# battery5_3.net
KiCad netlist of a schematic drawn in EAGLE
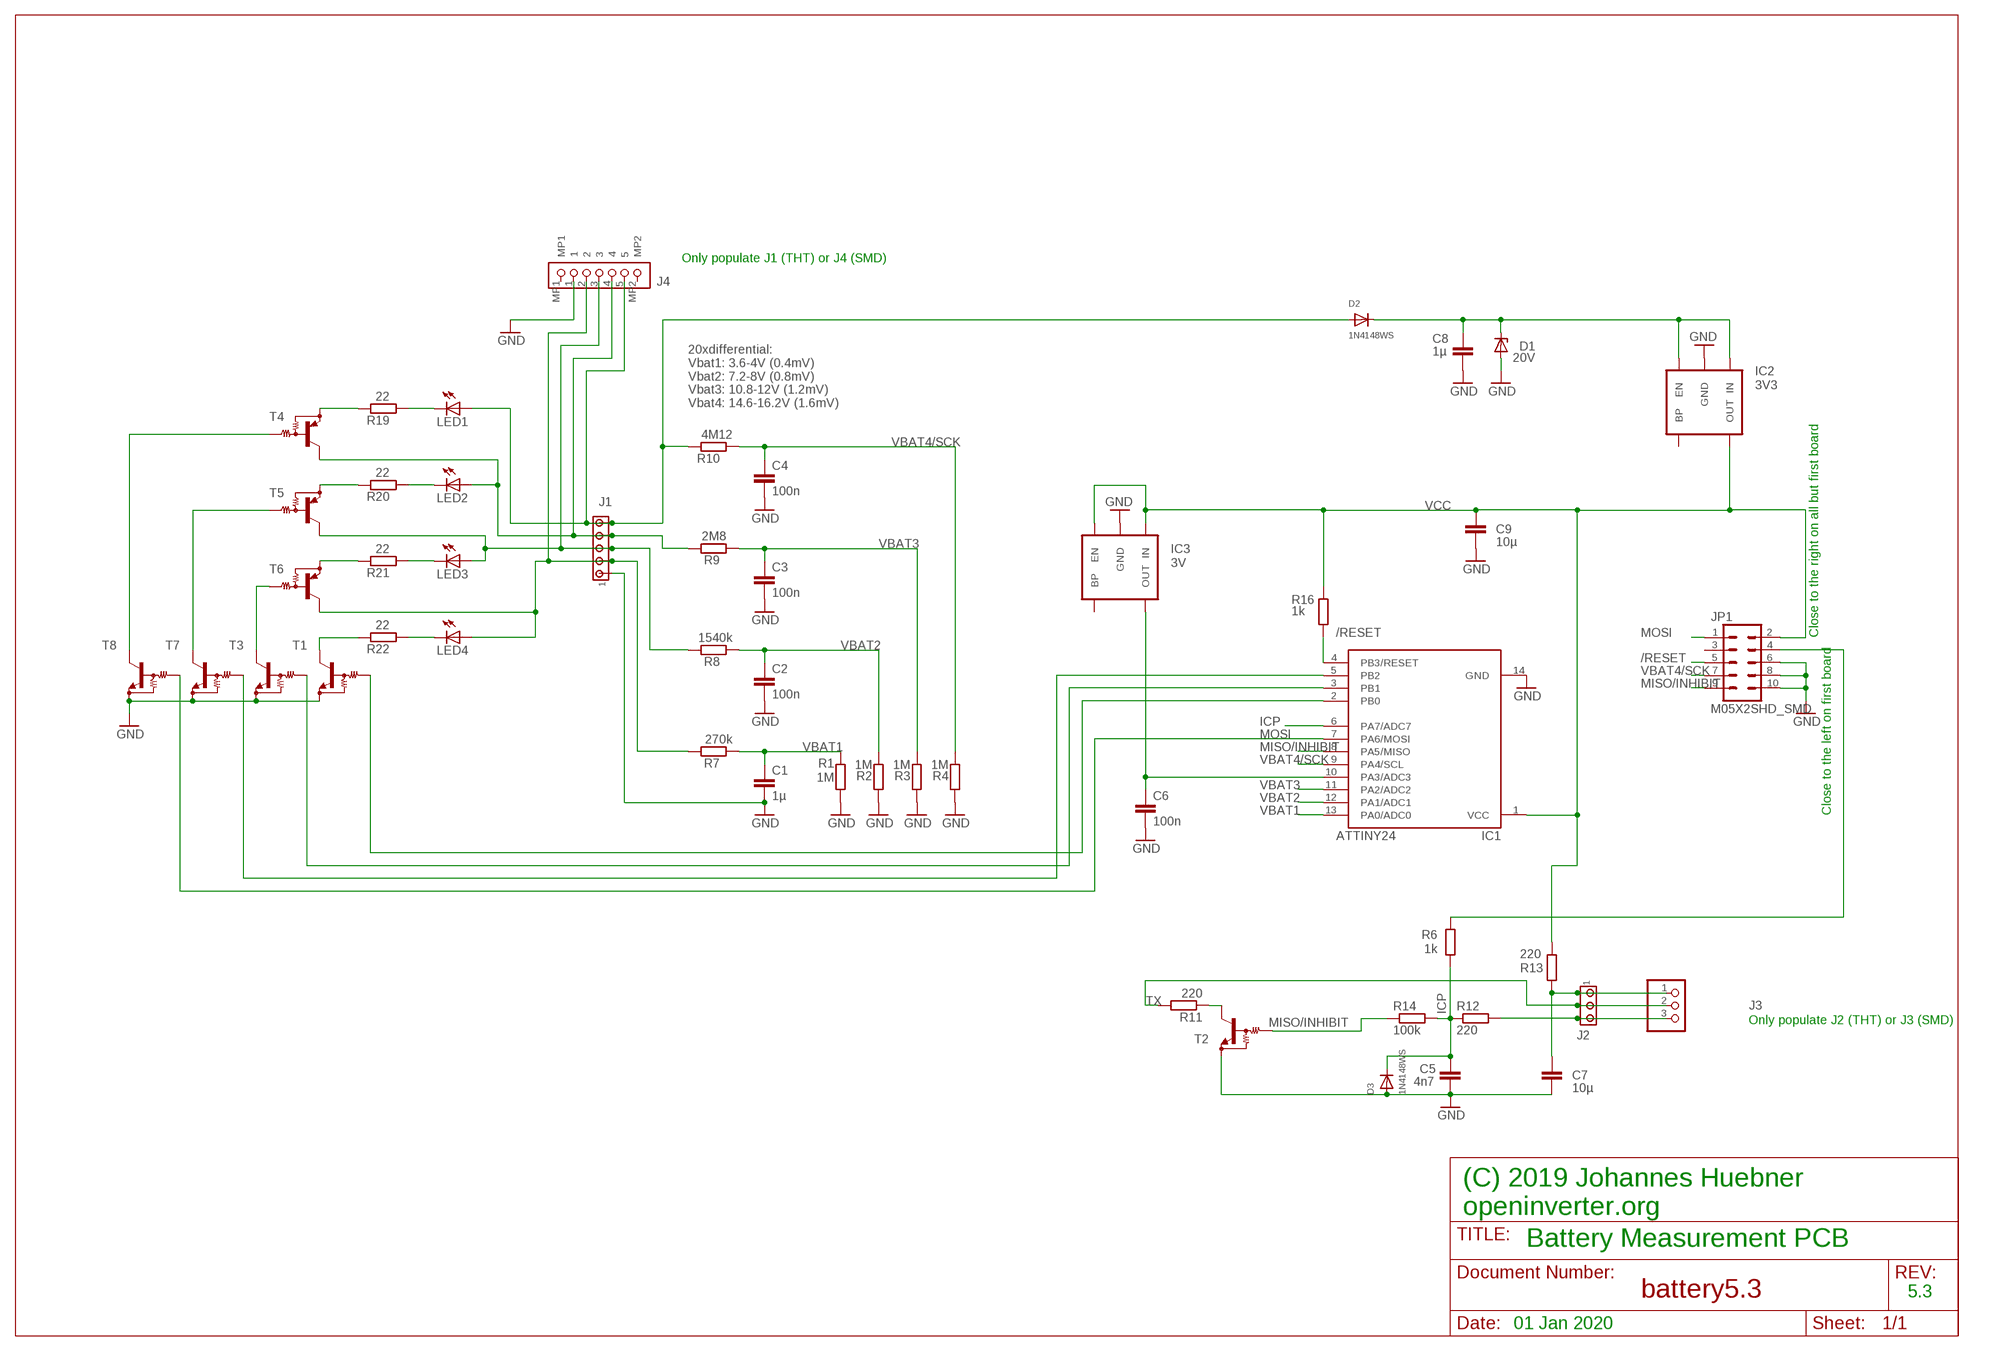
[diagram p0: schematic, sheet 1]

(export (version "E")
  (design (tool "Eeschema 10.0.6"))
  (components
    (comp (ref "C1")
      (value "1µ")
      (footprint "eagle-import:C0603")
      (libsource (lib "eagle-import") (part "C-EUC0603"))
    )
    (comp (ref "C2")
      (value "100n")
      (footprint "eagle-import:C0603")
      (libsource (lib "eagle-import") (part "C-EUC0603"))
    )
    (comp (ref "C3")
      (value "100n")
      (footprint "eagle-import:C0603")
      (libsource (lib "eagle-import") (part "C-EUC0603"))
    )
    (comp (ref "C4")
      (value "100n")
      (footprint "eagle-import:C0603")
      (libsource (lib "eagle-import") (part "C-EUC0603"))
    )
    (comp (ref "C5")
      (value "4n7")
      (footprint "eagle-import:C0603")
      (libsource (lib "eagle-import") (part "C-EUC0603"))
    )
    (comp (ref "C6")
      (value "100n")
      (footprint "eagle-import:C0603")
      (libsource (lib "eagle-import") (part "C-EUC0603"))
    )
    (comp (ref "C7")
      (value "10µ")
      (footprint "eagle-import:C0805")
      (libsource (lib "eagle-import") (part "C-EUC0805"))
    )
    (comp (ref "C8")
      (value "1µ")
      (footprint "eagle-import:C0805")
      (libsource (lib "eagle-import") (part "C-EUC0805"))
    )
    (comp (ref "C9")
      (value "10µ")
      (footprint "eagle-import:C0805")
      (libsource (lib "eagle-import") (part "C-EUC0805"))
    )
    (comp (ref "D1")
      (value "20V")
      (footprint "eagle-import:SMB")
      (libsource (lib "eagle-import") (part "ZENER-DIODESMB"))
    )
    (comp (ref "D2")
      (value "1N4148WS")
      (footprint "eagle-import:SOD-323F")
      (libsource (lib "eagle-import") (part "DIODESOD-323F"))
    )
    (comp (ref "D3")
      (value "1N4148WS")
      (footprint "eagle-import:SOD-323F")
      (libsource (lib "eagle-import") (part "DIODESOD-323F"))
    )
    (comp (ref "IC1")
      (value "ATTINY24")
      (footprint "eagle-import:SO014")
      (libsource (lib "eagle-import") (part "ATTINY24"))
    )
    (comp (ref "IC2")
      (value "3V3")
      (footprint "eagle-import:SOT23-5")
      (libsource (lib "eagle-import") (part "V_REG_LDOSMD"))
    )
    (comp (ref "IC3")
      (value "3V")
      (footprint "eagle-import:SOT23-5")
      (libsource (lib "eagle-import") (part "V_REG_LDOSMD"))
    )
    (comp (ref "J1")
      (value "MTA05-100")
      (footprint "eagle-import:10X05MTA")
      (libsource (lib "eagle-import") (part "MTA05-100"))
    )
    (comp (ref "J2")
      (value "MTA03-100")
      (footprint "eagle-import:10X03MTA")
      (libsource (lib "eagle-import") (part "MTA03-100"))
    )
    (comp (ref "J3")
      (value "JST_3PIN")
      (footprint "eagle-import:JSTPH3")
      (libsource (lib "eagle-import") (part "JST_3PIN"))
    )
    (comp (ref "J4")
      (value "BM05B-PASS-1-TFT_(LF)(SN)SMD")
      (footprint "eagle-import:BM05BPASS1TFTLFSN")
      (libsource (lib "eagle-import") (part "BM05B-PASS-1-TFT_(LF)(SN)SMD"))
    )
    (comp (ref "JP1")
      (value "M05X2SHD_SMD")
      (footprint "eagle-import:2X5-SHROUDED_SMD")
      (libsource (lib "eagle-import") (part "M05X2SHD_SMD"))
    )
    (comp (ref "LED1")
      (value "150060GS75000")
      (footprint "eagle-import:CHIPLED_0805")
      (libsource (lib "eagle-import") (part "LEDCHIPLED_0805"))
    )
    (comp (ref "LED2")
      (value "150060GS75000")
      (footprint "eagle-import:CHIPLED_0805")
      (libsource (lib "eagle-import") (part "LEDCHIPLED_0805"))
    )
    (comp (ref "LED3")
      (value "150060GS75000")
      (footprint "eagle-import:CHIPLED_0805")
      (libsource (lib "eagle-import") (part "LEDCHIPLED_0805"))
    )
    (comp (ref "LED4")
      (value "150060GS75000")
      (footprint "eagle-import:CHIPLED_0805")
      (libsource (lib "eagle-import") (part "LEDCHIPLED_0805"))
    )
    (comp (ref "R1")
      (value "1M")
      (footprint "eagle-import:R0603")
      (libsource (lib "eagle-import") (part "R-EU_R0603"))
    )
    (comp (ref "R2")
      (value "1M")
      (footprint "eagle-import:R0603")
      (libsource (lib "eagle-import") (part "R-EU_R0603"))
    )
    (comp (ref "R3")
      (value "1M")
      (footprint "eagle-import:R0603")
      (libsource (lib "eagle-import") (part "R-EU_R0603"))
    )
    (comp (ref "R4")
      (value "1M")
      (footprint "eagle-import:R0603")
      (libsource (lib "eagle-import") (part "R-EU_R0603"))
    )
    (comp (ref "R6")
      (value "1k")
      (footprint "eagle-import:R0603")
      (libsource (lib "eagle-import") (part "R-EU_R0603"))
    )
    (comp (ref "R7")
      (value "270k")
      (footprint "eagle-import:R0603")
      (libsource (lib "eagle-import") (part "R-EU_R0603"))
    )
    (comp (ref "R8")
      (value "1540k")
      (footprint "eagle-import:R0603")
      (libsource (lib "eagle-import") (part "R-EU_R0603"))
    )
    (comp (ref "R9")
      (value "2M8")
      (footprint "eagle-import:R0603")
      (libsource (lib "eagle-import") (part "R-EU_R0603"))
    )
    (comp (ref "R10")
      (value "4M12")
      (footprint "eagle-import:R0603")
      (libsource (lib "eagle-import") (part "R-EU_R0603"))
    )
    (comp (ref "R11")
      (value "220")
      (footprint "eagle-import:R0603")
      (libsource (lib "eagle-import") (part "R-EU_R0603"))
    )
    (comp (ref "R12")
      (value "220")
      (footprint "eagle-import:R0603")
      (libsource (lib "eagle-import") (part "R-EU_R0603"))
    )
    (comp (ref "R13")
      (value "220")
      (footprint "eagle-import:R0603")
      (libsource (lib "eagle-import") (part "R-EU_R0603"))
    )
    (comp (ref "R14")
      (value "100k")
      (footprint "eagle-import:R0603")
      (libsource (lib "eagle-import") (part "R-EU_R0603"))
    )
    (comp (ref "R16")
      (value "1k")
      (footprint "eagle-import:R0603")
      (libsource (lib "eagle-import") (part "R-EU_R0603"))
    )
    (comp (ref "R19")
      (value "22")
      (footprint "eagle-import:R0805")
      (libsource (lib "eagle-import") (part "R-EU_R0805"))
    )
    (comp (ref "R20")
      (value "22")
      (footprint "eagle-import:R0805")
      (libsource (lib "eagle-import") (part "R-EU_R0805"))
    )
    (comp (ref "R21")
      (value "22")
      (footprint "eagle-import:R0805")
      (libsource (lib "eagle-import") (part "R-EU_R0805"))
    )
    (comp (ref "R22")
      (value "22")
      (footprint "eagle-import:R0805")
      (libsource (lib "eagle-import") (part "R-EU_R0805"))
    )
    (comp (ref "T1")
      (value "MMUN2233")
      (footprint "eagle-import:SC59-BEC")
      (libsource (lib "eagle-import") (part "-NPN_DRIVER-SC59-BECMUN2211T1"))
    )
    (comp (ref "T2")
      (value "MMUN2233")
      (footprint "eagle-import:SC59-BEC")
      (libsource (lib "eagle-import") (part "-NPN_DRIVER-SC59-BECMUN2211T1"))
    )
    (comp (ref "T3")
      (value "MMUN2233")
      (footprint "eagle-import:SC59-BEC")
      (libsource (lib "eagle-import") (part "-NPN_DRIVER-SC59-BECMUN2211T1"))
    )
    (comp (ref "T4")
      (value "MMUN2111LT1G")
      (footprint "eagle-import:SC59-BEC")
      (libsource (lib "eagle-import") (part "-PNP_DRIVER-SC59-BECMUN2111T1"))
    )
    (comp (ref "T5")
      (value "MMUN2111LT1G")
      (footprint "eagle-import:SC59-BEC")
      (libsource (lib "eagle-import") (part "-PNP_DRIVER-SC59-BECMUN2111T1"))
    )
    (comp (ref "T6")
      (value "MMUN2111LT1G")
      (footprint "eagle-import:SC59-BEC")
      (libsource (lib "eagle-import") (part "-PNP_DRIVER-SC59-BECMUN2111T1"))
    )
    (comp (ref "T7")
      (value "MMUN2233")
      (footprint "eagle-import:SC59-BEC")
      (libsource (lib "eagle-import") (part "-NPN_DRIVER-SC59-BECMUN2211T1"))
    )
    (comp (ref "T8")
      (value "MMUN2233")
      (footprint "eagle-import:SC59-BEC")
      (libsource (lib "eagle-import") (part "-NPN_DRIVER-SC59-BECMUN2211T1"))
    )
  )
  (nets
    (net (code "1") (name "/ICP") (class "Default")
      (node (ref "C5") (pin "1") (pinfunction "1_1") (pintype "passive"))
      (node (ref "D3") (pin "C") (pinfunction "C_C") (pintype "passive"))
      (node (ref "IC1") (pin "6") (pinfunction "PA7/ADC7_6") (pintype "bidirectional"))
      (node (ref "R12") (pin "1") (pinfunction "1_1") (pintype "passive"))
      (node (ref "R14") (pin "2") (pinfunction "2_2") (pintype "passive"))
      (node (ref "R6") (pin "1") (pinfunction "1_1") (pintype "passive"))
    )
    (net (code "2") (name "/MISO{slash}INHIBIT") (class "Default")
      (node (ref "IC1") (pin "8") (pinfunction "PA5/MISO_8") (pintype "bidirectional"))
      (node (ref "JP1") (pin "9") (pinfunction "9_9") (pintype "passive"))
      (node (ref "R14") (pin "1") (pinfunction "1_1") (pintype "passive"))
      (node (ref "T2") (pin "B") (pinfunction "B_B") (pintype "passive"))
    )
    (net (code "3") (name "/MOSI") (class "Default")
      (node (ref "IC1") (pin "7") (pinfunction "PA6/MOSI_7") (pintype "bidirectional"))
      (node (ref "JP1") (pin "1") (pinfunction "1_1") (pintype "passive"))
      (node (ref "T8") (pin "B") (pinfunction "B_B") (pintype "passive"))
    )
    (net (code "4") (name "/TX") (class "Default")
      (node (ref "J2") (pin "2") (pinfunction "2_2") (pintype "passive"))
      (node (ref "J3") (pin "2") (pinfunction "2_2") (pintype "passive"))
      (node (ref "R11") (pin "2") (pinfunction "2_2") (pintype "passive"))
    )
    (net (code "5") (name "/VBAT1") (class "Default")
      (node (ref "C1") (pin "1") (pinfunction "1_1") (pintype "passive"))
      (node (ref "IC1") (pin "13") (pinfunction "PA0/ADC0_13") (pintype "bidirectional"))
      (node (ref "R1") (pin "1") (pinfunction "1_1") (pintype "passive"))
      (node (ref "R7") (pin "1") (pinfunction "1_1") (pintype "passive"))
    )
    (net (code "6") (name "/VBAT2") (class "Default")
      (node (ref "C2") (pin "1") (pinfunction "1_1") (pintype "passive"))
      (node (ref "IC1") (pin "12") (pinfunction "PA1/ADC1_12") (pintype "bidirectional"))
      (node (ref "R2") (pin "1") (pinfunction "1_1") (pintype "passive"))
      (node (ref "R8") (pin "1") (pinfunction "1_1") (pintype "passive"))
    )
    (net (code "7") (name "/VBAT3") (class "Default")
      (node (ref "C3") (pin "1") (pinfunction "1_1") (pintype "passive"))
      (node (ref "IC1") (pin "11") (pinfunction "PA2/ADC2_11") (pintype "bidirectional"))
      (node (ref "R3") (pin "1") (pinfunction "1_1") (pintype "passive"))
      (node (ref "R9") (pin "1") (pinfunction "1_1") (pintype "passive"))
    )
    (net (code "8") (name "/VBAT4{slash}SCK") (class "Default")
      (node (ref "C4") (pin "1") (pinfunction "1_1") (pintype "passive"))
      (node (ref "IC1") (pin "9") (pinfunction "PA4/SCL_9") (pintype "bidirectional"))
      (node (ref "JP1") (pin "7") (pinfunction "7_7") (pintype "passive"))
      (node (ref "R10") (pin "1") (pinfunction "1_1") (pintype "passive"))
      (node (ref "R4") (pin "1") (pinfunction "1_1") (pintype "passive"))
    )
    (net (code "9") (name "/VCC") (class "Default")
      (node (ref "C9") (pin "1") (pinfunction "1_1") (pintype "passive"))
      (node (ref "IC1") (pin "1") (pinfunction "VCC_1") (pintype "bidirectional"))
      (node (ref "IC2") (pin "5") (pinfunction "OUT_5") (pintype "passive"))
      (node (ref "IC3") (pin "1") (pinfunction "IN_1") (pintype "input"))
      (node (ref "IC3") (pin "3") (pinfunction "EN_3") (pintype "input"))
      (node (ref "JP1") (pin "2") (pinfunction "2_2") (pintype "passive"))
      (node (ref "R13") (pin "1") (pinfunction "1_1") (pintype "passive"))
      (node (ref "R16") (pin "1") (pinfunction "1_1") (pintype "passive"))
    )
    (net (code "10") (name "/{slash}RESET") (class "Default")
      (node (ref "IC1") (pin "4") (pinfunction "PB3/RESET_4") (pintype "bidirectional"))
      (node (ref "JP1") (pin "5") (pinfunction "5_5") (pintype "passive"))
      (node (ref "R16") (pin "2") (pinfunction "2_2") (pintype "passive"))
    )
    (net (code "11") (name "GND") (class "Default")
      (node (ref "C1") (pin "2") (pinfunction "2_2") (pintype "passive"))
      (node (ref "C2") (pin "2") (pinfunction "2_2") (pintype "passive"))
      (node (ref "C3") (pin "2") (pinfunction "2_2") (pintype "passive"))
      (node (ref "C4") (pin "2") (pinfunction "2_2") (pintype "passive"))
      (node (ref "C5") (pin "2") (pinfunction "2_2") (pintype "passive"))
      (node (ref "C6") (pin "2") (pinfunction "2_2") (pintype "passive"))
      (node (ref "C7") (pin "2") (pinfunction "2_2") (pintype "passive"))
      (node (ref "C8") (pin "2") (pinfunction "2_2") (pintype "passive"))
      (node (ref "C9") (pin "2") (pinfunction "2_2") (pintype "passive"))
      (node (ref "D1") (pin "A") (pinfunction "A_A") (pintype "passive"))
      (node (ref "D3") (pin "A") (pinfunction "A_A") (pintype "passive"))
      (node (ref "IC1") (pin "14") (pinfunction "GND_14") (pintype "bidirectional"))
      (node (ref "IC2") (pin "2") (pinfunction "GND_2") (pintype "input"))
      (node (ref "IC3") (pin "2") (pinfunction "GND_2") (pintype "input"))
      (node (ref "J1") (pin "1") (pinfunction "1_1") (pintype "passive"))
      (node (ref "J4") (pin "1") (pinfunction "1_1") (pintype "bidirectional"))
      (node (ref "JP1") (pin "10") (pinfunction "10_10") (pintype "passive"))
      (node (ref "JP1") (pin "6") (pinfunction "6_6") (pintype "passive"))
      (node (ref "JP1") (pin "8") (pinfunction "8_8") (pintype "passive"))
      (node (ref "R1") (pin "2") (pinfunction "2_2") (pintype "passive"))
      (node (ref "R2") (pin "2") (pinfunction "2_2") (pintype "passive"))
      (node (ref "R3") (pin "2") (pinfunction "2_2") (pintype "passive"))
      (node (ref "R4") (pin "2") (pinfunction "2_2") (pintype "passive"))
      (node (ref "T1") (pin "E") (pinfunction "E_E") (pintype "passive"))
      (node (ref "T2") (pin "E") (pinfunction "E_E") (pintype "passive"))
      (node (ref "T3") (pin "E") (pinfunction "E_E") (pintype "passive"))
      (node (ref "T7") (pin "E") (pinfunction "E_E") (pintype "passive"))
      (node (ref "T8") (pin "E") (pinfunction "E_E") (pintype "passive"))
    )
    (net (code "12") (name "Net-(C7-Pad1)") (class "Default")
      (node (ref "C7") (pin "1") (pinfunction "1_1") (pintype "passive"))
      (node (ref "J2") (pin "1") (pinfunction "1_1") (pintype "passive"))
      (node (ref "J3") (pin "1") (pinfunction "1_1") (pintype "passive"))
      (node (ref "R13") (pin "2") (pinfunction "2_2") (pintype "passive"))
    )
    (net (code "13") (name "Net-(D2-PadA)") (class "Default")
      (node (ref "D2") (pin "A") (pinfunction "A_A") (pintype "passive"))
      (node (ref "J1") (pin "5") (pinfunction "5_5") (pintype "passive"))
      (node (ref "J4") (pin "5") (pinfunction "5_5") (pintype "bidirectional"))
      (node (ref "LED1") (pin "A") (pinfunction "A_A") (pintype "passive"))
      (node (ref "R10") (pin "2") (pinfunction "2_2") (pintype "passive"))
    )
    (net (code "14") (name "Net-(IC1-PA3{slash}ADC3)") (class "Default")
      (node (ref "C6") (pin "1") (pinfunction "1_1") (pintype "passive"))
      (node (ref "IC1") (pin "10") (pinfunction "PA3/ADC3_10") (pintype "bidirectional"))
      (node (ref "IC3") (pin "5") (pinfunction "OUT_5") (pintype "passive"))
    )
    (net (code "15") (name "Net-(IC1-PB0)") (class "Default")
      (node (ref "IC1") (pin "2") (pinfunction "PB0_2") (pintype "bidirectional"))
      (node (ref "T1") (pin "B") (pinfunction "B_B") (pintype "passive"))
    )
    (net (code "16") (name "Net-(IC1-PB1)") (class "Default")
      (node (ref "IC1") (pin "3") (pinfunction "PB1_3") (pintype "bidirectional"))
      (node (ref "T3") (pin "B") (pinfunction "B_B") (pintype "passive"))
    )
    (net (code "17") (name "Net-(IC1-PB2)") (class "Default")
      (node (ref "IC1") (pin "5") (pinfunction "PB2_5") (pintype "bidirectional"))
      (node (ref "T7") (pin "B") (pinfunction "B_B") (pintype "passive"))
    )
    (net (code "18") (name "Net-(IC2-EN)") (class "Default")
      (node (ref "C8") (pin "1") (pinfunction "1_1") (pintype "passive"))
      (node (ref "D1") (pin "C") (pinfunction "C_C") (pintype "passive"))
      (node (ref "D2") (pin "C") (pinfunction "C_C") (pintype "passive"))
      (node (ref "IC2") (pin "1") (pinfunction "IN_1") (pintype "input"))
      (node (ref "IC2") (pin "3") (pinfunction "EN_3") (pintype "input"))
    )
    (net (code "19") (name "Net-(J1-Pad2)") (class "Default")
      (node (ref "J1") (pin "2") (pinfunction "2_2") (pintype "passive"))
      (node (ref "J4") (pin "2") (pinfunction "2_2") (pintype "bidirectional"))
      (node (ref "LED4") (pin "A") (pinfunction "A_A") (pintype "passive"))
      (node (ref "R7") (pin "2") (pinfunction "2_2") (pintype "passive"))
      (node (ref "T6") (pin "C") (pinfunction "C_C") (pintype "passive"))
    )
    (net (code "20") (name "Net-(J1-Pad3)") (class "Default")
      (node (ref "J1") (pin "3") (pinfunction "3_3") (pintype "passive"))
      (node (ref "J4") (pin "3") (pinfunction "3_3") (pintype "bidirectional"))
      (node (ref "LED3") (pin "A") (pinfunction "A_A") (pintype "passive"))
      (node (ref "R8") (pin "2") (pinfunction "2_2") (pintype "passive"))
      (node (ref "T5") (pin "C") (pinfunction "C_C") (pintype "passive"))
    )
    (net (code "21") (name "Net-(J1-Pad4)") (class "Default")
      (node (ref "J1") (pin "4") (pinfunction "4_4") (pintype "passive"))
      (node (ref "J4") (pin "4") (pinfunction "4_4") (pintype "bidirectional"))
      (node (ref "LED2") (pin "A") (pinfunction "A_A") (pintype "passive"))
      (node (ref "R9") (pin "2") (pinfunction "2_2") (pintype "passive"))
      (node (ref "T4") (pin "C") (pinfunction "C_C") (pintype "passive"))
    )
    (net (code "22") (name "Net-(J2-Pad3)") (class "Default")
      (node (ref "J2") (pin "3") (pinfunction "3_3") (pintype "passive"))
      (node (ref "J3") (pin "3") (pinfunction "3_3") (pintype "passive"))
      (node (ref "R12") (pin "2") (pinfunction "2_2") (pintype "passive"))
    )
    (net (code "23") (name "Net-(JP1-Pad4)") (class "Default")
      (node (ref "JP1") (pin "4") (pinfunction "4_4") (pintype "passive"))
      (node (ref "R6") (pin "2") (pinfunction "2_2") (pintype "passive"))
    )
    (net (code "24") (name "Net-(LED1-PadC)") (class "Default")
      (node (ref "LED1") (pin "C") (pinfunction "C_C") (pintype "passive"))
      (node (ref "R19") (pin "1") (pinfunction "1_1") (pintype "passive"))
    )
    (net (code "25") (name "Net-(LED2-PadC)") (class "Default")
      (node (ref "LED2") (pin "C") (pinfunction "C_C") (pintype "passive"))
      (node (ref "R20") (pin "1") (pinfunction "1_1") (pintype "passive"))
    )
    (net (code "26") (name "Net-(LED3-PadC)") (class "Default")
      (node (ref "LED3") (pin "C") (pinfunction "C_C") (pintype "passive"))
      (node (ref "R21") (pin "1") (pinfunction "1_1") (pintype "passive"))
    )
    (net (code "27") (name "Net-(LED4-PadC)") (class "Default")
      (node (ref "LED4") (pin "C") (pinfunction "C_C") (pintype "passive"))
      (node (ref "R22") (pin "1") (pinfunction "1_1") (pintype "passive"))
    )
    (net (code "28") (name "Net-(R11-Pad1)") (class "Default")
      (node (ref "R11") (pin "1") (pinfunction "1_1") (pintype "passive"))
      (node (ref "T2") (pin "C") (pinfunction "C_C") (pintype "passive"))
    )
    (net (code "29") (name "Net-(R19-Pad2)") (class "Default")
      (node (ref "R19") (pin "2") (pinfunction "2_2") (pintype "passive"))
      (node (ref "T4") (pin "E") (pinfunction "E_E") (pintype "passive"))
    )
    (net (code "30") (name "Net-(R20-Pad2)") (class "Default")
      (node (ref "R20") (pin "2") (pinfunction "2_2") (pintype "passive"))
      (node (ref "T5") (pin "E") (pinfunction "E_E") (pintype "passive"))
    )
    (net (code "31") (name "Net-(R21-Pad2)") (class "Default")
      (node (ref "R21") (pin "2") (pinfunction "2_2") (pintype "passive"))
      (node (ref "T6") (pin "E") (pinfunction "E_E") (pintype "passive"))
    )
    (net (code "32") (name "Net-(R22-Pad2)") (class "Default")
      (node (ref "R22") (pin "2") (pinfunction "2_2") (pintype "passive"))
      (node (ref "T1") (pin "C") (pinfunction "C_C") (pintype "passive"))
    )
    (net (code "33") (name "Net-(T3-PadC)") (class "Default")
      (node (ref "T3") (pin "C") (pinfunction "C_C") (pintype "passive"))
      (node (ref "T6") (pin "B") (pinfunction "B_B") (pintype "passive"))
    )
    (net (code "34") (name "Net-(T4-PadB)") (class "Default")
      (node (ref "T4") (pin "B") (pinfunction "B_B") (pintype "passive"))
      (node (ref "T8") (pin "C") (pinfunction "C_C") (pintype "passive"))
    )
    (net (code "35") (name "Net-(T5-PadB)") (class "Default")
      (node (ref "T5") (pin "B") (pinfunction "B_B") (pintype "passive"))
      (node (ref "T7") (pin "C") (pinfunction "C_C") (pintype "passive"))
    )
    (net (code "36") (name "unconnected-(IC2-BP-Pad4)") (class "Default")
      (node (ref "IC2") (pin "4") (pinfunction "BP_4") (pintype "input"))
    )
    (net (code "37") (name "unconnected-(IC3-BP-Pad4)") (class "Default")
      (node (ref "IC3") (pin "4") (pinfunction "BP_4") (pintype "input"))
    )
    (net (code "38") (name "unconnected-(J4-PadMP1)") (class "Default")
      (node (ref "J4") (pin "MP1") (pinfunction "MP1_MP1") (pintype "bidirectional"))
    )
    (net (code "39") (name "unconnected-(J4-PadMP2)") (class "Default")
      (node (ref "J4") (pin "MP2") (pinfunction "MP2_MP2") (pintype "bidirectional"))
    )
    (net (code "40") (name "unconnected-(JP1-Pad3)") (class "Default")
      (node (ref "JP1") (pin "3") (pinfunction "3_3") (pintype "passive"))
    )
  )
)
